# Microcontroller.net
KiCad netlist of a schematic drawn in Altium Designer
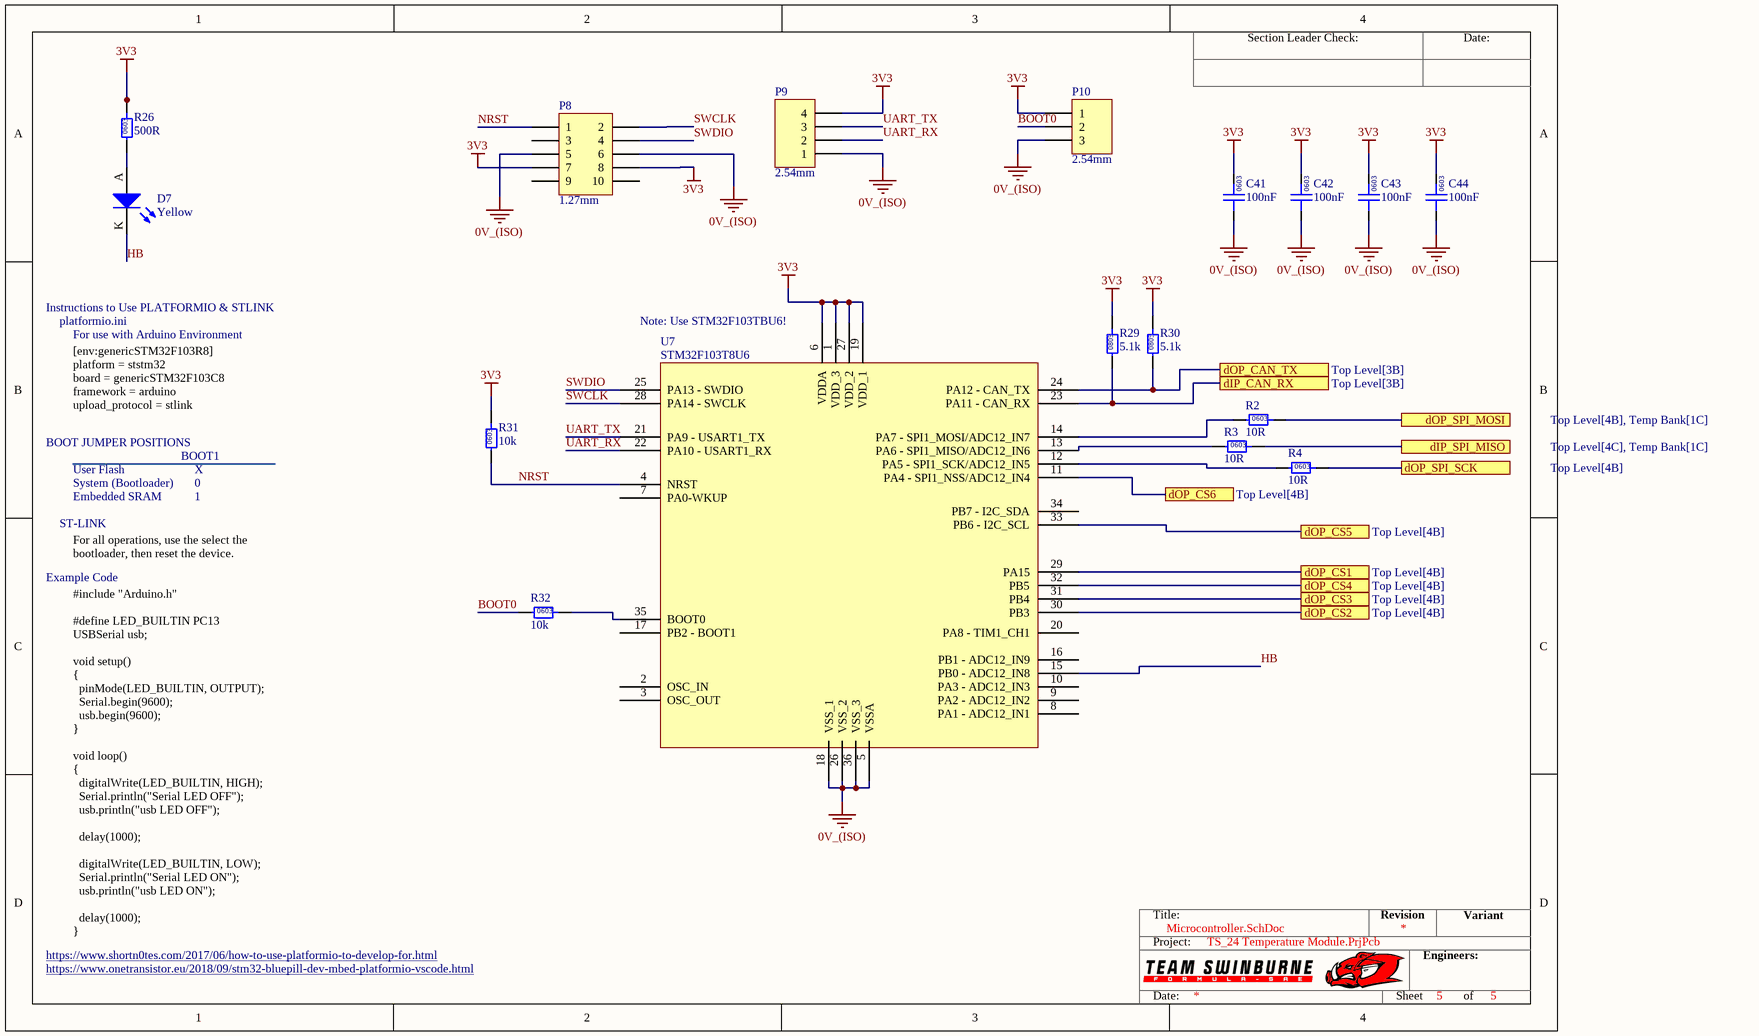
[diagram p0: Microcontroller.SchDoc]

(export (version "E")
  (design (tool "Eeschema 10.0.6"))
  (components
    (comp (ref "C41")
      (value "100nF")
      (footprint "0603")
      (fields
        (field (name "PART NUMBER") "GCM188L81H104KA57D")
        (field (name "MANUFACTURER") "muRata")
        (field (name "TOLERANCE") "±10%")
      )
      (libsource (lib "ts_standard_library") (part "Capacitor 0603"))
    )
    (comp (ref "C42")
      (value "100nF")
      (footprint "0603")
      (fields
        (field (name "PART NUMBER") "GCM188L81H104KA57D")
        (field (name "MANUFACTURER") "muRata")
        (field (name "TOLERANCE") "±10%")
      )
      (libsource (lib "ts_standard_library") (part "Capacitor 0603"))
    )
    (comp (ref "C43")
      (value "100nF")
      (footprint "0603")
      (fields
        (field (name "PART NUMBER") "GCM188L81H104KA57D")
        (field (name "MANUFACTURER") "muRata")
        (field (name "TOLERANCE") "±10%")
      )
      (libsource (lib "ts_standard_library") (part "Capacitor 0603"))
    )
    (comp (ref "C44")
      (value "100nF")
      (footprint "0603")
      (fields
        (field (name "PART NUMBER") "GCM188L81H104KA57D")
        (field (name "MANUFACTURER") "muRata")
        (field (name "TOLERANCE") "±10%")
      )
      (libsource (lib "ts_standard_library") (part "Capacitor 0603"))
    )
    (comp (ref "D7")
      (value "Yellow")
      (footprint "0805 LED")
      (description "Yellow LED Indication - Discrete 1.75V 0805 (2012 Metric)")
      (fields (field (name "PART NUMBER") "SML-211YTT86") (field (name "MANUFACTURER") "ROHM Semiconductor"))
      (libsource (lib "ts_standard_library") (part "LED"))
    )
    (comp (ref "P8")
      (value "1.27mm")
      (footprint "3221-10-0300-00")
      (fields
        (field (name "PART NUMBER") "SMD 1.27mm Header 2x5 (3221-10-0300-00)")
        (field (name "CONTACT") "NA")
      )
      (libsource (lib "ts_standard_connectors") (part "Header 2x5"))
    )
    (comp (ref "P9")
      (value "2.54mm")
      (footprint "TH 2.54mm Header 1x4")
      (fields (field (name "PART NUMBER") "TH 2.54mm Header 1x4") (field (name "CONTACT") "NA"))
      (libsource (lib "ts_standard_connectors") (part "Header 1x4"))
    )
    (comp (ref "P10")
      (value "2.54mm")
      (footprint "TH 2.54mm Header 1x3")
      (fields (field (name "PART NUMBER") "TH 2.54mm Header 1x3") (field (name "CONTACT") "NA"))
      (libsource (lib "ts_standard_connectors") (part "Header 1x3"))
    )
    (comp (ref "R2")
      (value "10R")
      (footprint "0603")
      (fields
        (field (name "PART NUMBER") "RC0603FR-0710RL")
        (field (name "MANUFACTURER") "YAGEO")
        (field (name "TOLERANCE") "0.01")
      )
      (libsource (lib "ts_standard_library") (part "Resistor 0603"))
    )
    (comp (ref "R3")
      (value "10R")
      (footprint "0603")
      (fields
        (field (name "PART NUMBER") "RC0603FR-0710RL")
        (field (name "MANUFACTURER") "YAGEO")
        (field (name "TOLERANCE") "0.01")
      )
      (libsource (lib "ts_standard_library") (part "Resistor 0603"))
    )
    (comp (ref "R4")
      (value "10R")
      (footprint "0603")
      (fields
        (field (name "PART NUMBER") "RC0603FR-0710RL")
        (field (name "MANUFACTURER") "YAGEO")
        (field (name "TOLERANCE") "0.01")
      )
      (libsource (lib "ts_standard_library") (part "Resistor 0603"))
    )
    (comp (ref "R26")
      (value "500R")
      (footprint "0603")
      (fields
        (field (name "PART NUMBER") "RT0603BRD07500RL")
        (field (name "MANUFACTURER") "YAGEO")
        (field (name "TOLERANCE") "0.01")
      )
      (libsource (lib "ts_standard_library") (part "Resistor 0603"))
    )
    (comp (ref "R29")
      (value "5.1k")
      (footprint "0805")
      (fields
        (field (name "PART NUMBER") "RC0805FR075K1L")
        (field (name "MANUFACTURER") "YAGEO")
        (field (name "TOLERANCE") "0.01")
      )
      (libsource (lib "ts_standard_library") (part "Resistor 0805"))
    )
    (comp (ref "R30")
      (value "5.1k")
      (footprint "0805")
      (fields
        (field (name "PART NUMBER") "RC0805FR075K1L")
        (field (name "MANUFACTURER") "YAGEO")
        (field (name "TOLERANCE") "0.01")
      )
      (libsource (lib "ts_standard_library") (part "Resistor 0805"))
    )
    (comp (ref "R31")
      (value "10k")
      (footprint "0603")
      (fields
        (field (name "PART NUMBER") "RC0603FR-0710KL")
        (field (name "MANUFACTURER") "YAGEO")
        (field (name "TOLERANCE") "0.01")
      )
      (libsource (lib "ts_standard_library") (part "Resistor 0603"))
    )
    (comp (ref "R32")
      (value "10k")
      (footprint "0603")
      (fields
        (field (name "PART NUMBER") "RC0603FR-0710KL")
        (field (name "MANUFACTURER") "YAGEO")
        (field (name "TOLERANCE") "0.01")
      )
      (libsource (lib "ts_standard_library") (part "Resistor 0603"))
    )
    (comp (ref "U7")
      (value "STM32F103T8U6")
      (footprint "STM_QFN-36")
      (description "ARM® Cortex®-M3 STM32F1 Microcontroller IC 32-Bit 72MHz 64KB (64K x 8) FLASH QFN")
      (fields (field (name "MANUFACTURER") "ST Microelectronics"))
      (libsource (lib "ts_standard_library") (part "STM32F103T8U6"))
    )
  )
  (nets
    (net (code "1") (name "/BOOT0") (class "Default")
      (node (ref "P10") (pin "2") (pinfunction "2_2") (pintype "passive"))
      (node (ref "R32") (pin "1") (pinfunction "1_1") (pintype "passive"))
    )
    (net (code "2") (name "/HB") (class "Default")
      (node (ref "D7") (pin "K") (pinfunction "K_K") (pintype "passive"))
      (node (ref "U7") (pin "15") (pinfunction "PB0_-_ADC12_IN8_15") (pintype "passive"))
    )
    (net (code "3") (name "/NRST") (class "Default")
      (node (ref "P8") (pin "1") (pinfunction "1_1") (pintype "passive"))
      (node (ref "R31") (pin "1") (pinfunction "1_1") (pintype "passive"))
      (node (ref "U7") (pin "4") (pinfunction "NRST_4") (pintype "passive"))
    )
    (net (code "4") (name "/SWCLK") (class "Default")
      (node (ref "P8") (pin "2") (pinfunction "2_2") (pintype "passive"))
      (node (ref "U7") (pin "28") (pinfunction "PA14_-_SWCLK_28") (pintype "passive"))
    )
    (net (code "5") (name "/SWDIO") (class "Default")
      (node (ref "P8") (pin "4") (pinfunction "4_4") (pintype "passive"))
      (node (ref "U7") (pin "25") (pinfunction "PA13_-_SWDIO_25") (pintype "passive"))
    )
    (net (code "6") (name "/UART_RX") (class "Default")
      (node (ref "P9") (pin "2") (pinfunction "2_2") (pintype "passive"))
      (node (ref "U7") (pin "22") (pinfunction "PA10_-_USART1_RX_22") (pintype "passive"))
    )
    (net (code "7") (name "/UART_TX") (class "Default")
      (node (ref "P9") (pin "3") (pinfunction "3_3") (pintype "passive"))
      (node (ref "U7") (pin "21") (pinfunction "PA9_-_USART1_TX_21") (pintype "passive"))
    )
    (net (code "8") (name "/dIP_CAN_RX") (class "Default")
      (node (ref "R29") (pin "1") (pinfunction "1_1") (pintype "passive"))
      (node (ref "U7") (pin "23") (pinfunction "PA11_-_CAN_RX_23") (pintype "passive"))
    )
    (net (code "9") (name "/dIP_SPI_MISO") (class "Default")
      (node (ref "R3") (pin "2") (pinfunction "2_2") (pintype "passive"))
    )
    (net (code "10") (name "/dOP_CAN_TX") (class "Default")
      (node (ref "R30") (pin "1") (pinfunction "1_1") (pintype "passive"))
      (node (ref "U7") (pin "24") (pinfunction "PA12_-_CAN_TX_24") (pintype "passive"))
    )
    (net (code "11") (name "/dOP_CS1") (class "Default")
      (node (ref "U7") (pin "29") (pinfunction "PA15_29") (pintype "passive"))
    )
    (net (code "12") (name "/dOP_CS2") (class "Default")
      (node (ref "U7") (pin "30") (pinfunction "PB3_30") (pintype "passive"))
    )
    (net (code "13") (name "/dOP_CS3") (class "Default")
      (node (ref "U7") (pin "31") (pinfunction "PB4_31") (pintype "passive"))
    )
    (net (code "14") (name "/dOP_CS4") (class "Default")
      (node (ref "U7") (pin "32") (pinfunction "PB5_32") (pintype "passive"))
    )
    (net (code "15") (name "/dOP_CS5") (class "Default")
      (node (ref "U7") (pin "33") (pinfunction "PB6_-_I2C_SCL_33") (pintype "passive"))
    )
    (net (code "16") (name "/dOP_CS6") (class "Default")
      (node (ref "U7") (pin "11") (pinfunction "PA4_-_SPI1_NSS/ADC12_IN4_11") (pintype "passive"))
    )
    (net (code "17") (name "/dOP_SPI_MOSI") (class "Default")
      (node (ref "R2") (pin "2") (pinfunction "2_2") (pintype "passive"))
    )
    (net (code "18") (name "/dOP_SPI_SCK") (class "Default")
      (node (ref "R4") (pin "2") (pinfunction "2_2") (pintype "passive"))
    )
    (net (code "19") (name "0V_(ISO)") (class "Default")
      (node (ref "C41") (pin "1") (pinfunction "1_1") (pintype "passive"))
      (node (ref "C42") (pin "1") (pinfunction "1_1") (pintype "passive"))
      (node (ref "C43") (pin "1") (pinfunction "1_1") (pintype "passive"))
      (node (ref "C44") (pin "1") (pinfunction "1_1") (pintype "passive"))
      (node (ref "P10") (pin "3") (pinfunction "3_3") (pintype "passive"))
      (node (ref "P8") (pin "5") (pinfunction "5_5") (pintype "passive"))
      (node (ref "P8") (pin "6") (pinfunction "6_6") (pintype "passive"))
      (node (ref "P9") (pin "1") (pinfunction "1_1") (pintype "passive"))
      (node (ref "U7") (pin "18") (pinfunction "VSS_1_18") (pintype "passive"))
      (node (ref "U7") (pin "26") (pinfunction "VSS_2_26") (pintype "passive"))
      (node (ref "U7") (pin "36") (pinfunction "VSS_3_36") (pintype "passive"))
      (node (ref "U7") (pin "5") (pinfunction "VSSA_5") (pintype "passive"))
    )
    (net (code "20") (name "3V3") (class "Default")
      (node (ref "C41") (pin "2") (pinfunction "2_2") (pintype "passive"))
      (node (ref "C42") (pin "2") (pinfunction "2_2") (pintype "passive"))
      (node (ref "C43") (pin "2") (pinfunction "2_2") (pintype "passive"))
      (node (ref "C44") (pin "2") (pinfunction "2_2") (pintype "passive"))
      (node (ref "P10") (pin "1") (pinfunction "1_1") (pintype "passive"))
      (node (ref "P8") (pin "7") (pinfunction "7_7") (pintype "passive"))
      (node (ref "P8") (pin "8") (pinfunction "8_8") (pintype "passive"))
      (node (ref "P9") (pin "4") (pinfunction "4_4") (pintype "passive"))
      (node (ref "R26") (pin "2") (pinfunction "2_2") (pintype "passive"))
      (node (ref "R29") (pin "2") (pinfunction "2_2") (pintype "passive"))
      (node (ref "R30") (pin "2") (pinfunction "2_2") (pintype "passive"))
      (node (ref "R31") (pin "2") (pinfunction "2_2") (pintype "passive"))
      (node (ref "U7") (pin "1") (pinfunction "VDD_3_1") (pintype "passive"))
      (node (ref "U7") (pin "19") (pinfunction "VDD_1_19") (pintype "passive"))
      (node (ref "U7") (pin "27") (pinfunction "VDD_2_27") (pintype "passive"))
      (node (ref "U7") (pin "6") (pinfunction "VDDA_6") (pintype "passive"))
    )
    (net (code "21") (name "Net-(D7-PadA)") (class "Default")
      (node (ref "D7") (pin "A") (pinfunction "A_A") (pintype "passive"))
      (node (ref "R26") (pin "1") (pinfunction "1_1") (pintype "passive"))
    )
    (net (code "22") (name "Net-(U7-BOOT0)") (class "Default")
      (node (ref "R32") (pin "2") (pinfunction "2_2") (pintype "passive"))
      (node (ref "U7") (pin "35") (pinfunction "BOOT0_35") (pintype "passive"))
    )
    (net (code "23") (name "Net-(U7-PA5_-_SPI1_SCK{slash}ADC12_IN5)") (class "Default")
      (node (ref "R4") (pin "1") (pinfunction "1_1") (pintype "passive"))
      (node (ref "U7") (pin "12") (pinfunction "PA5_-_SPI1_SCK/ADC12_IN5_12") (pintype "passive"))
    )
    (net (code "24") (name "Net-(U7-PA6_-_SPI1_MISO{slash}ADC12_IN6)") (class "Default")
      (node (ref "R3") (pin "1") (pinfunction "1_1") (pintype "passive"))
      (node (ref "U7") (pin "13") (pinfunction "PA6_-_SPI1_MISO/ADC12_IN6_13") (pintype "passive"))
    )
    (net (code "25") (name "Net-(U7-PA7_-_SPI1_MOSI{slash}ADC12_IN7)") (class "Default")
      (node (ref "R2") (pin "1") (pinfunction "1_1") (pintype "passive"))
      (node (ref "U7") (pin "14") (pinfunction "PA7_-_SPI1_MOSI/ADC12_IN7_14") (pintype "passive"))
    )
    (net (code "26") (name "unconnected-(P8-Pad3)") (class "Default")
      (node (ref "P8") (pin "3") (pinfunction "3_3") (pintype "passive"))
    )
    (net (code "27") (name "unconnected-(P8-Pad9)") (class "Default")
      (node (ref "P8") (pin "9") (pinfunction "9_9") (pintype "passive"))
    )
    (net (code "28") (name "unconnected-(P8-Pad10)") (class "Default")
      (node (ref "P8") (pin "10") (pinfunction "10_10") (pintype "passive"))
    )
    (net (code "29") (name "unconnected-(U7-OSC_IN-Pad2)") (class "Default")
      (node (ref "U7") (pin "2") (pinfunction "OSC_IN_2") (pintype "passive"))
    )
    (net (code "30") (name "unconnected-(U7-OSC_OUT-Pad3)") (class "Default")
      (node (ref "U7") (pin "3") (pinfunction "OSC_OUT_3") (pintype "passive"))
    )
    (net (code "31") (name "unconnected-(U7-PA0-WKUP-Pad7)") (class "Default")
      (node (ref "U7") (pin "7") (pinfunction "PA0-WKUP_7") (pintype "passive"))
    )
    (net (code "32") (name "unconnected-(U7-PA1_-_ADC12_IN1-Pad8)") (class "Default")
      (node (ref "U7") (pin "8") (pinfunction "PA1_-_ADC12_IN1_8") (pintype "passive"))
    )
    (net (code "33") (name "unconnected-(U7-PA2_-_ADC12_IN2-Pad9)") (class "Default")
      (node (ref "U7") (pin "9") (pinfunction "PA2_-_ADC12_IN2_9") (pintype "passive"))
    )
    (net (code "34") (name "unconnected-(U7-PA3_-_ADC12_IN3-Pad10)") (class "Default")
      (node (ref "U7") (pin "10") (pinfunction "PA3_-_ADC12_IN3_10") (pintype "passive"))
    )
    (net (code "35") (name "unconnected-(U7-PA8_-_TIM1_CH1-Pad20)") (class "Default")
      (node (ref "U7") (pin "20") (pinfunction "PA8_-_TIM1_CH1_20") (pintype "passive"))
    )
    (net (code "36") (name "unconnected-(U7-PB1_-_ADC12_IN9-Pad16)") (class "Default")
      (node (ref "U7") (pin "16") (pinfunction "PB1_-_ADC12_IN9_16") (pintype "passive"))
    )
    (net (code "37") (name "unconnected-(U7-PB2_-_BOOT1-Pad17)") (class "Default")
      (node (ref "U7") (pin "17") (pinfunction "PB2_-_BOOT1_17") (pintype "passive"))
    )
    (net (code "38") (name "unconnected-(U7-PB7_-_I2C_SDA-Pad34)") (class "Default")
      (node (ref "U7") (pin "34") (pinfunction "PB7_-_I2C_SDA_34") (pintype "passive"))
    )
  )
)
